# 555timer_pwm.net
KiCad netlist of a schematic drawn in EAGLE
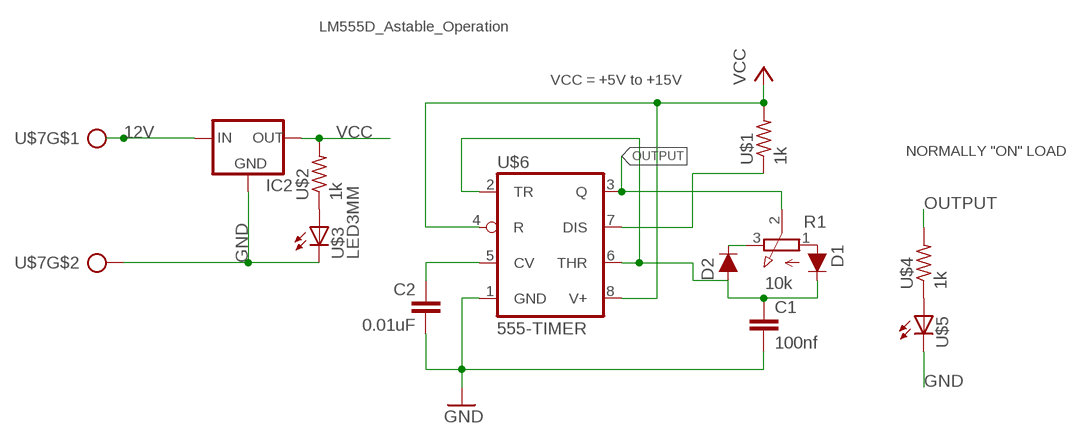
[diagram p0: schematic, sheet 1]

(export (version "E")
  (design (tool "Eeschema 10.0.6"))
  (components
    (comp (ref "C1")
      (value "100nf")
      (footprint "eagle-import:C025-025X050")
      (libsource (lib "eagle-import") (part "CAPACITOR"))
    )
    (comp (ref "C2")
      (value "0.01uF")
      (footprint "eagle-import:C025-025X050")
      (libsource (lib "eagle-import") (part "CAPACITOR"))
    )
    (comp (ref "D1")
      (value "200mA/100V/1V")
      (footprint "eagle-import:DIODE-1N4148")
      (libsource (lib "eagle-import") (part "DIODE(1A)-1N4148"))
    )
    (comp (ref "D2")
      (value "200mA/100V/1V")
      (footprint "eagle-import:DIODE-1N4148")
      (libsource (lib "eagle-import") (part "DIODE(1A)-1N4148"))
    )
    (comp (ref "IC2")
      (value "78XXS")
      (footprint "eagle-import:78XXS")
      (libsource (lib "eagle-import") (part "78XXS"))
    )
    (comp (ref "R1")
      (value "10k")
      (footprint "eagle-import:3RP_1610N")
      (libsource (lib "eagle-import") (part "POTENTIOMETER"))
    )
    (comp (ref "U$1")
      (value "1k")
      (footprint "eagle-import:0204_5")
      (libsource (lib "eagle-import") (part "RES-5"))
    )
    (comp (ref "U$2")
      (value "1k")
      (footprint "eagle-import:0204_5")
      (libsource (lib "eagle-import") (part "RES-5"))
    )
    (comp (ref "U$3")
      (value "LED3MM")
      (footprint "eagle-import:LED3MM")
      (libsource (lib "eagle-import") (part "LED3MM"))
    )
    (comp (ref "U$4")
      (value "1k")
      (footprint "eagle-import:0204_5")
      (libsource (lib "eagle-import") (part "RES-5"))
    )
    (comp (ref "U$5")
      (value "LED3MM")
      (footprint "eagle-import:LED3MM")
      (libsource (lib "eagle-import") (part "LED3MM"))
    )
    (comp (ref "U$6")
      (value "555-TIMER")
      (footprint "eagle-import:DIL08")
      (libsource (lib "eagle-import") (part "555-TIMER"))
    )
    (comp (ref "U$7")
      (value "CON_PTR_2")
      (footprint "eagle-import:AK300_2")
      (libsource (lib "eagle-import") (part "CON_PTR_2"))
    )
  )
  (nets
    (net (code "1") (name "/12V") (class "Default")
      (node (ref "IC2") (pin "IN") (pinfunction "IN_IN") (pintype "input"))
      (node (ref "U$7") (pin "1") (pinfunction "KL_1") (pintype "passive"))
    )
    (net (code "2") (name "GND") (class "Default")
      (node (ref "C1") (pin "2") (pinfunction "2_2") (pintype "passive"))
      (node (ref "C2") (pin "2") (pinfunction "2_2") (pintype "passive"))
      (node (ref "IC2") (pin "GND") (pinfunction "GND_GND") (pintype "input"))
      (node (ref "U$3") (pin "K") (pinfunction "C_K") (pintype "passive"))
      (node (ref "U$5") (pin "K") (pinfunction "C_K") (pintype "passive"))
      (node (ref "U$6") (pin "1") (pinfunction "GND_1") (pintype "power_in"))
      (node (ref "U$7") (pin "2") (pinfunction "KL_2") (pintype "passive"))
    )
    (net (code "3") (name "Net-(R1-A)") (class "Default")
      (node (ref "D1") (pin "A") (pinfunction "A_A") (pintype "passive"))
      (node (ref "R1") (pin "1") (pinfunction "A_1") (pintype "passive"))
    )
    (net (code "4") (name "Net-(R1-E)") (class "Default")
      (node (ref "D2") (pin "C") (pinfunction "C_C") (pintype "passive"))
      (node (ref "R1") (pin "3") (pinfunction "E_3") (pintype "passive"))
    )
    (net (code "5") (name "Net-(U$2-Pad1)") (class "Default")
      (node (ref "U$2") (pin "1") (pinfunction "1_1") (pintype "passive"))
      (node (ref "U$3") (pin "A") (pinfunction "A_A") (pintype "passive"))
    )
    (net (code "6") (name "Net-(U$4-Pad1)") (class "Default")
      (node (ref "U$4") (pin "1") (pinfunction "1_1") (pintype "passive"))
      (node (ref "U$5") (pin "A") (pinfunction "A_A") (pintype "passive"))
    )
    (net (code "7") (name "Net-(U$6-CV)") (class "Default")
      (node (ref "C2") (pin "1") (pinfunction "1_1") (pintype "passive"))
      (node (ref "U$6") (pin "5") (pinfunction "CV_5") (pintype "input"))
    )
    (net (code "8") (name "Net-(U$6-DIS)") (class "Default")
      (node (ref "U$1") (pin "1") (pinfunction "1_1") (pintype "passive"))
      (node (ref "U$6") (pin "7") (pinfunction "DIS_7") (pintype "input"))
    )
    (net (code "9") (name "Net-(U$6-THR)") (class "Default")
      (node (ref "C1") (pin "1") (pinfunction "1_1") (pintype "passive"))
      (node (ref "D1") (pin "C") (pinfunction "C_C") (pintype "passive"))
      (node (ref "D2") (pin "A") (pinfunction "A_A") (pintype "passive"))
      (node (ref "U$6") (pin "2") (pinfunction "TR_2") (pintype "input"))
      (node (ref "U$6") (pin "6") (pinfunction "THR_6") (pintype "input"))
    )
    (net (code "10") (name "OUTPUT") (class "Default")
      (node (ref "R1") (pin "2") (pinfunction "S_2") (pintype "passive"))
      (node (ref "U$4") (pin "2") (pinfunction "2_2") (pintype "passive"))
      (node (ref "U$6") (pin "3") (pinfunction "Q_3") (pintype "output"))
    )
    (net (code "11") (name "VCC") (class "Default")
      (node (ref "IC2") (pin "OUT") (pinfunction "OUT_OUT") (pintype "passive"))
      (node (ref "U$1") (pin "2") (pinfunction "2_2") (pintype "passive"))
      (node (ref "U$2") (pin "2") (pinfunction "2_2") (pintype "passive"))
      (node (ref "U$6") (pin "4") (pinfunction "R_4") (pintype "input"))
      (node (ref "U$6") (pin "8") (pinfunction "V+_8") (pintype "power_in"))
    )
  )
)
